# cSLIM-SA_power.net
KiCad netlist of a schematic drawn in Altium Designer
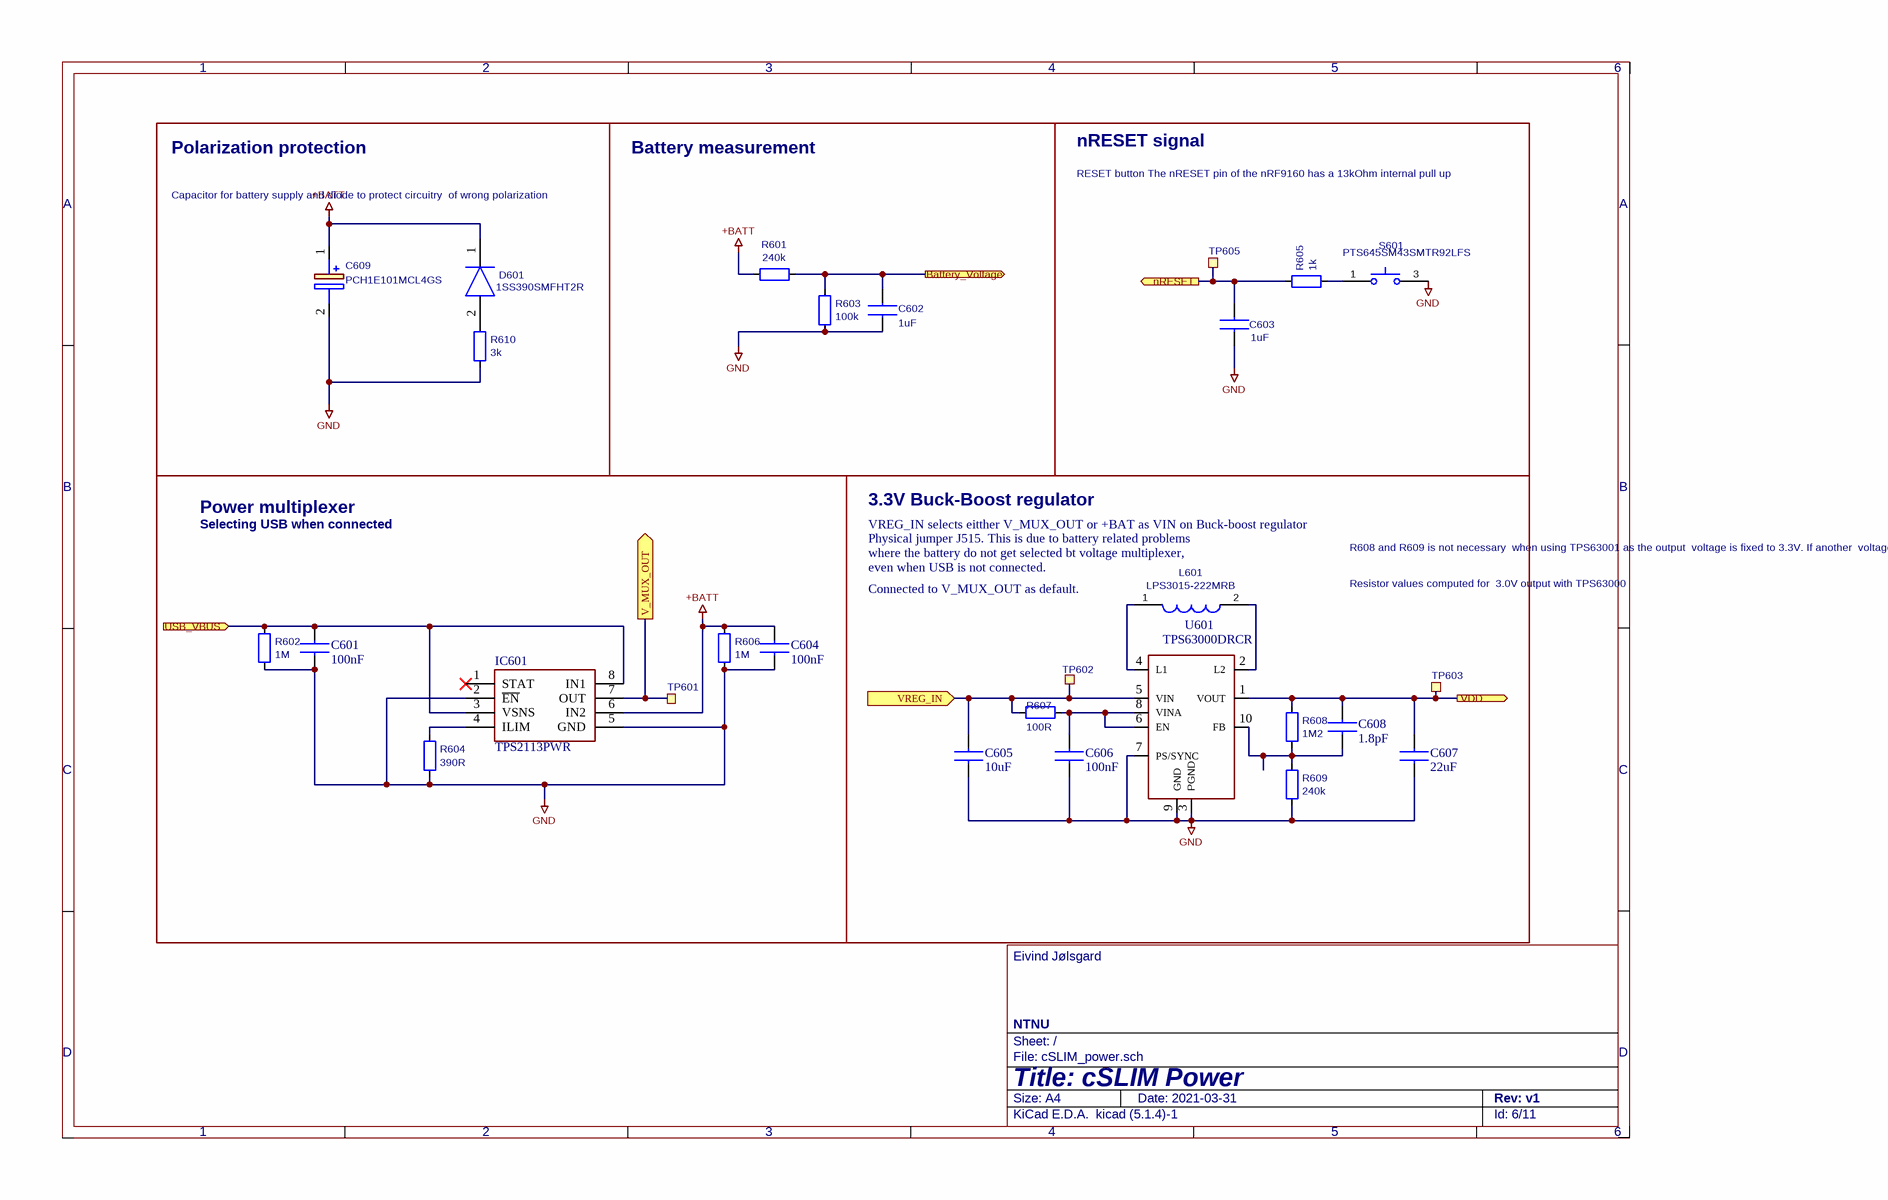
[diagram p0: cSLIM-SA_power.SchDoc]

(export (version "E")
  (design (tool "Eeschema 10.0.6"))
  (components
    (comp (ref "C601")
      (value "100nF")
      (footprint "cSLIM-SA:CAPC1608X90N")
      (description "Capacitor")
      (fields
        (field (name "MANUFACTURER_PART_NUMBER") "06033G104ZAT2A")
        (field (name "MOUSER PART NUMBER") "581-06033G104Z")
      )
      (libsource (lib "cSLIM-SA") (part "C"))
    )
    (comp (ref "C602")
      (value "1uF")
      (footprint "cSLIM-SA:CAPC1608X90N")
      (description "Capacitor")
      (fields
        (field (name "MANUFACTURER_PART_NUMBER") "06033G104ZAT2A")
        (field (name "MOUSER PART NUMBER") "581-06033G104Z")
      )
      (libsource (lib "cSLIM-SA") (part "C"))
    )
    (comp (ref "C603")
      (value "1uF")
      (footprint "cSLIM-SA:CAPC1608X90N")
      (description "Capacitor")
      (fields
        (field (name "MANUFACTURER_PART_NUMBER") "06033G104ZAT2A")
        (field (name "MOUSER PART NUMBER") "581-06033G104Z")
      )
      (libsource (lib "cSLIM-SA") (part "C"))
    )
    (comp (ref "C604")
      (value "100nF")
      (footprint "cSLIM-SA:CAPC1608X90N")
      (description "Capacitor")
      (fields
        (field (name "MANUFACTURER_PART_NUMBER") "06033G104ZAT2A")
        (field (name "MOUSER PART NUMBER") "581-06033G104Z")
      )
      (libsource (lib "cSLIM-SA") (part "C"))
    )
    (comp (ref "C605")
      (value "10uF")
      (footprint "cSLIM-SA:CAPC1608X90N")
      (description "Capacitor")
      (fields
        (field (name "MANUFACTURER_PART_NUMBER") "06033G104ZAT2A")
        (field (name "MOUSER PART NUMBER") "581-06033G104Z")
      )
      (libsource (lib "cSLIM-SA") (part "C"))
    )
    (comp (ref "C606")
      (value "100nF")
      (footprint "cSLIM-SA:CAPC1608X90N")
      (description "Capacitor")
      (fields
        (field (name "MANUFACTURER_PART_NUMBER") "06033G104ZAT2A")
        (field (name "MOUSER PART NUMBER") "581-06033G104Z")
      )
      (libsource (lib "cSLIM-SA") (part "C"))
    )
    (comp (ref "C607")
      (value "22uF")
      (footprint "cSLIM-SA:CAPC1608X90N")
      (description "Capacitor")
      (fields
        (field (name "MANUFACTURER_PART_NUMBER") "06033G104ZAT2A")
        (field (name "MOUSER PART NUMBER") "581-06033G104Z")
      )
      (libsource (lib "cSLIM-SA") (part "C"))
    )
    (comp (ref "C608")
      (value "1.8pF")
      (footprint "cSLIM-SA:CAPC1608X90N")
      (description "Capacitor")
      (fields
        (field (name "MANUFACTURER_PART_NUMBER") "06033G104ZAT2A")
        (field (name "MOUSER PART NUMBER") "581-06033G104Z")
      )
      (libsource (lib "cSLIM-SA") (part "C"))
    )
    (comp (ref "C609")
      (value "PCH1E101MCL4GS")
      (footprint "cSLIM-SA:CAPAE660X840N")
      (description "Capacitor Polarised")
      (fields (field (name "MOUSER PART NUMBER") "647-PCH1E101MCL4GS"))
      (libsource (lib "*") (part "PCH1E101MCL4GS"))
    )
    (comp (ref "D601")
      (value "1SS390SMFHT2R")
      (footprint "cSLIM-SA:SODFL1608X70N")
      (description "Diode")
      (fields (field (name "MOUSER PART NUMBER") "755-1SS390SMFHT2R"))
      (libsource (lib "cSLIM-SA") (part "1SS390SMFHT2R"))
    )
    (comp (ref "IC601")
      (value "TPS2113PWR")
      (footprint "cSLIM-SA:SOP65P640X120-8N")
      (description "Integrated Circuit")
      (fields (field (name "MOUSER PART NUMBER") "595-TPS2113PWR"))
      (libsource (lib "cSLIM-SA") (part "TPS2113PWR"))
    )
    (comp (ref "L601")
      (value "LPS3015-222MRB")
      (footprint "LPS3015")
      (fields
        (field (name "MOUSER PART NUMBER") "994-LPS3015-103MRB")
        (field (name "MANUFACTURER_PART_NUMBER") "LPS3015-103MRB")
      )
      (libsource (lib "cSLIM-SA") (part "LPS3015-103MRB"))
    )
    (comp (ref "R601") (value "240k") (footprint "RESC1608X55N") (libsource (lib "cSLIM-SA") (part "R")))
    (comp (ref "R602") (value "1M") (footprint "RESC1608X55N") (libsource (lib "") (part "R_1")))
    (comp (ref "R603") (value "100k") (footprint "RESC1608X55N") (libsource (lib "") (part "R_1")))
    (comp (ref "R604") (value "390R") (footprint "RESC1608X55N") (libsource (lib "") (part "R_1")))
    (comp (ref "R605") (value "1k") (footprint "RESC1608X55N") (libsource (lib "") (part "R_2")))
    (comp (ref "R606") (value "1M") (footprint "RESC1608X55N") (libsource (lib "") (part "R_1")))
    (comp (ref "R607") (value "100R") (footprint "RESC1608X55N") (libsource (lib "cSLIM-SA") (part "R")))
    (comp (ref "R608") (value "1M2") (footprint "RESC1608X55N") (libsource (lib "") (part "R_1")))
    (comp (ref "R609") (value "240k") (footprint "RESC1608X55N") (libsource (lib "") (part "R_1")))
    (comp (ref "R610") (value "3k") (footprint "RESC1608X55N") (libsource (lib "") (part "R_1")))
    (comp (ref "S601")
      (value "PTS645SM43SMTR92LFS")
      (footprint "PTS645(SMT)")
      (description "Switch 4-pi. used 1-3 (2-4 not in use)")
      (fields
        (field (name "MOUSER PART NUMBER") "611-TLSA070JLFS")
        (field (name "MANUFACTURER_PART_NUMBER") "TLS A 070J LFS")
      )
      (libsource (lib "cSLIM-SA") (part "PTS645SM43SMTR92LFS"))
    )
    (comp (ref "TP601") (value "~") (footprint "cSLIM-SA:TP_SMD_Ø1.0mm") (libsource (lib "") (part "TP_1")))
    (comp (ref "TP602")
      (value "~")
      (footprint "cSLIM-SA:TP_SMD_Ø1.0mm")
      (libsource (lib "cSLIM-SA") (part "TP"))
    )
    (comp (ref "TP603")
      (value "~")
      (footprint "cSLIM-SA:TP_SMD_Ø1.0mm")
      (libsource (lib "cSLIM-SA") (part "TP"))
    )
    (comp (ref "TP605")
      (value "~")
      (footprint "cSLIM-SA:TP_SMD_Ø1.0mm")
      (libsource (lib "cSLIM-SA") (part "TP"))
    )
    (comp (ref "U601")
      (value "TPS63000DRCR")
      (footprint "cSLIM-SA:TPS63002DRCR")
      (description "Integrated Circuit")
      (fields (field (name "MOUSER PART NUMBER") "595-TPS63000DRCR"))
      (libsource (lib "cSLIM-SA") (part "TPS63000DRCR"))
    )
  )
  (nets
    (net (code "1") (name "+BATT") (class "Default")
      (node (ref "C604") (pin "1") (pinfunction "1_1") (pintype "passive"))
      (node (ref "C609") (pin "1") (pinfunction "+_1") (pintype "passive"))
      (node (ref "D601") (pin "1") (pinfunction "K_1") (pintype "passive"))
      (node (ref "IC601") (pin "6") (pinfunction "IN2_6") (pintype "passive"))
      (node (ref "R601") (pin "2") (pinfunction "2_2") (pintype "passive"))
      (node (ref "R606") (pin "1") (pinfunction "1_1") (pintype "passive"))
    )
    (net (code "2") (name "/Battery_Voltage") (class "Default")
      (node (ref "C602") (pin "1") (pinfunction "1_1") (pintype "passive"))
      (node (ref "R601") (pin "1") (pinfunction "1_1") (pintype "passive"))
      (node (ref "R603") (pin "1") (pinfunction "1_1") (pintype "passive"))
    )
    (net (code "3") (name "/USB_VBUS") (class "Default")
      (node (ref "C601") (pin "1") (pinfunction "1_1") (pintype "passive"))
      (node (ref "IC601") (pin "3") (pinfunction "VSNS_3") (pintype "passive"))
      (node (ref "IC601") (pin "8") (pinfunction "IN1_8") (pintype "passive"))
      (node (ref "R602") (pin "1") (pinfunction "1_1") (pintype "passive"))
    )
    (net (code "4") (name "/VDD") (class "Default")
      (node (ref "C607") (pin "1") (pinfunction "1_1") (pintype "passive"))
      (node (ref "C608") (pin "1") (pinfunction "1_1") (pintype "passive"))
      (node (ref "R608") (pin "1") (pinfunction "1_1") (pintype "passive"))
      (node (ref "TP603") (pin "1") (pinfunction "1_1") (pintype "passive"))
      (node (ref "U601") (pin "1") (pinfunction "VOUT_1") (pintype "passive"))
    )
    (net (code "5") (name "/VREG_IN") (class "Default")
      (node (ref "C605") (pin "1") (pinfunction "1_1") (pintype "passive"))
      (node (ref "R607") (pin "2") (pinfunction "2_2") (pintype "passive"))
      (node (ref "TP602") (pin "1") (pinfunction "1_1") (pintype "passive"))
      (node (ref "U601") (pin "5") (pinfunction "VIN_5") (pintype "passive"))
    )
    (net (code "6") (name "/V_MUX_OUT") (class "Default")
      (node (ref "IC601") (pin "7") (pinfunction "OUT_7") (pintype "passive"))
      (node (ref "TP601") (pin "1") (pinfunction "1_1") (pintype "passive"))
    )
    (net (code "7") (name "/nRESET") (class "Default")
      (node (ref "C603") (pin "1") (pinfunction "1_1") (pintype "passive"))
      (node (ref "R605") (pin "1") (pinfunction "1_1") (pintype "passive"))
      (node (ref "TP605") (pin "1") (pinfunction "1_1") (pintype "passive"))
    )
    (net (code "8") (name "GND") (class "Default")
      (node (ref "C601") (pin "2") (pinfunction "2_2") (pintype "passive"))
      (node (ref "C602") (pin "2") (pinfunction "2_2") (pintype "passive"))
      (node (ref "C603") (pin "2") (pinfunction "2_2") (pintype "passive"))
      (node (ref "C604") (pin "2") (pinfunction "2_2") (pintype "passive"))
      (node (ref "C605") (pin "2") (pinfunction "2_2") (pintype "passive"))
      (node (ref "C606") (pin "2") (pinfunction "2_2") (pintype "passive"))
      (node (ref "C607") (pin "2") (pinfunction "2_2") (pintype "passive"))
      (node (ref "C609") (pin "2") (pinfunction "-_2") (pintype "passive"))
      (node (ref "IC601") (pin "2") (pinfunction "~{EN}_2") (pintype "passive"))
      (node (ref "IC601") (pin "5") (pinfunction "GND_5") (pintype "passive"))
      (node (ref "R602") (pin "2") (pinfunction "2_2") (pintype "passive"))
      (node (ref "R603") (pin "2") (pinfunction "2_2") (pintype "passive"))
      (node (ref "R604") (pin "2") (pinfunction "2_2") (pintype "passive"))
      (node (ref "R606") (pin "2") (pinfunction "2_2") (pintype "passive"))
      (node (ref "R609") (pin "2") (pinfunction "2_2") (pintype "passive"))
      (node (ref "R610") (pin "2") (pinfunction "2_2") (pintype "passive"))
      (node (ref "S601") (pin "3") (pinfunction "3_3") (pintype "passive"))
      (node (ref "U601") (pin "3") (pinfunction "PGND_3") (pintype "passive"))
      (node (ref "U601") (pin "7") (pinfunction "PS/SYNC_7") (pintype "passive"))
      (node (ref "U601") (pin "9") (pinfunction "GND_9") (pintype "passive"))
    )
    (net (code "9") (name "Net-(D601-A)") (class "Default")
      (node (ref "D601") (pin "2") (pinfunction "A_2") (pintype "passive"))
      (node (ref "R610") (pin "1") (pinfunction "1_1") (pintype "passive"))
    )
    (net (code "10") (name "Net-(IC601-ILIM)") (class "Default")
      (node (ref "IC601") (pin "4") (pinfunction "ILIM_4") (pintype "passive"))
      (node (ref "R604") (pin "1") (pinfunction "1_1") (pintype "passive"))
    )
    (net (code "11") (name "Net-(R605-Pad2)") (class "Default")
      (node (ref "R605") (pin "2") (pinfunction "2_2") (pintype "passive"))
      (node (ref "S601") (pin "1") (pinfunction "1_1") (pintype "passive"))
    )
    (net (code "12") (name "Net-(U601-EN)") (class "Default")
      (node (ref "C606") (pin "1") (pinfunction "1_1") (pintype "passive"))
      (node (ref "R607") (pin "1") (pinfunction "1_1") (pintype "passive"))
      (node (ref "U601") (pin "6") (pinfunction "EN_6") (pintype "passive"))
      (node (ref "U601") (pin "8") (pinfunction "VINA_8") (pintype "passive"))
    )
    (net (code "13") (name "Net-(U601-FB)") (class "Default")
      (node (ref "C608") (pin "2") (pinfunction "2_2") (pintype "passive"))
      (node (ref "R608") (pin "2") (pinfunction "2_2") (pintype "passive"))
      (node (ref "R609") (pin "1") (pinfunction "1_1") (pintype "passive"))
      (node (ref "U601") (pin "10") (pinfunction "FB_10") (pintype "passive"))
    )
    (net (code "14") (name "Net-(U601-L1)") (class "Default")
      (node (ref "L601") (pin "1") (pinfunction "1_1") (pintype "passive"))
      (node (ref "U601") (pin "4") (pinfunction "L1_4") (pintype "passive"))
    )
    (net (code "15") (name "Net-(U601-L2)") (class "Default")
      (node (ref "L601") (pin "2") (pinfunction "2_2") (pintype "passive"))
      (node (ref "U601") (pin "2") (pinfunction "L2_2") (pintype "passive"))
    )
    (net (code "16") (name "unconnected-(IC601-STAT-Pad1)") (class "Default")
      (node (ref "IC601") (pin "1") (pinfunction "STAT_1") (pintype "passive+no_connect"))
    )
  )
)
